# Underwater_ROV_ESCS_asc.net
KiCad netlist of a schematic drawn in Altium Designer
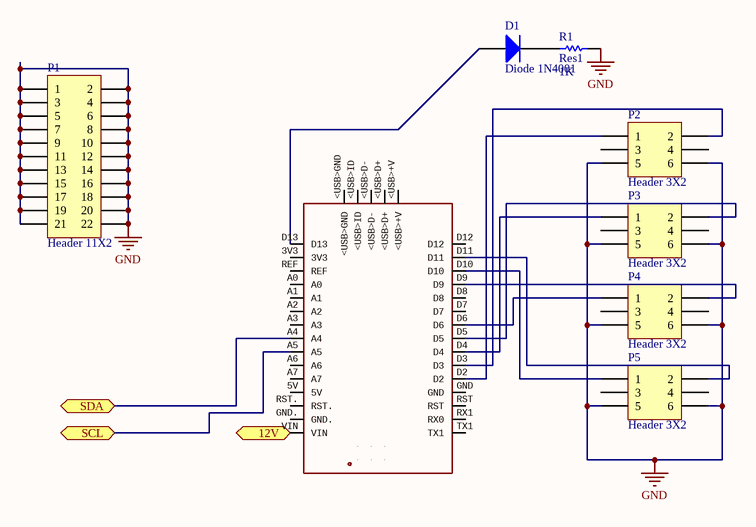
[diagram p0: Underwater_ROV_ESCS_asc.SchDoc]

(export (version "E")
  (design (tool "Eeschema 10.0.6"))
  (components
    (comp (ref "D1")
      (value "Diode 1N4001")
      (footprint "DO-41")
      (description "1 Amp General Purpose Rectifier")
      (fields (field (name "PUBLISHER") "Altium Limited"))
      (libsource (lib "Miscellaneous Devices") (part "Diode 1N4001"))
    )
    (comp (ref "Nano_ESC")
      (value "Device for representing an Arduino Nano board with a footprint in an EAGLE design. Created by Dave Young for Element14. More EAGLE documentation at: http://www.element14.com/community/community/knode/cadsoft_eagle")
      (footprint "ARDUINO_NANO")
      (libsource (lib "E14_Arduino_revC") (part "ARDUINO_NANO"))
    )
    (comp (ref "P1")
      (value "Header 11X2")
      (footprint "HDR2X11")
      (description "Header, 11-Pin, Dual row")
      (fields (field (name "PUBLISHER") "Altium Limited"))
      (libsource (lib "Miscellaneous Connectors") (part "Header 11X2"))
    )
    (comp (ref "P2")
      (value "Header 3X2")
      (footprint "HDR2X3")
      (description "Header, 3-Pin, Dual row")
      (fields (field (name "PUBLISHER") "Altium Limited"))
      (libsource (lib "Miscellaneous Connectors") (part "Header 3X2"))
    )
    (comp (ref "P3")
      (value "Header 3X2")
      (footprint "HDR2X3")
      (description "Header, 3-Pin, Dual row")
      (fields (field (name "PUBLISHER") "Altium Limited"))
      (libsource (lib "Miscellaneous Connectors") (part "Header 3X2"))
    )
    (comp (ref "P4")
      (value "Header 3X2")
      (footprint "HDR2X3")
      (description "Header, 3-Pin, Dual row")
      (fields (field (name "PUBLISHER") "Altium Limited"))
      (libsource (lib "Miscellaneous Connectors") (part "Header 3X2"))
    )
    (comp (ref "P5")
      (value "Header 3X2")
      (footprint "HDR2X3")
      (description "Header, 3-Pin, Dual row")
      (fields (field (name "PUBLISHER") "Altium Limited"))
      (libsource (lib "Miscellaneous Connectors") (part "Header 3X2"))
    )
    (comp (ref "R1")
      (value "Res1")
      (footprint "AXIAL-0.3")
      (description "Resistor")
      (fields (field (name "ALTIUM_VALUE") "1K") (field (name "PUBLISHER") "Altium Limited"))
      (libsource (lib "Miscellaneous Devices") (part "Res1"))
    )
  )
  (nets
    (net (code "1") (name "/12V") (class "Default")
      (node (ref "Nano_ESC") (pin "VIN") (pinfunction "VIN_VIN") (pintype "passive"))
    )
    (net (code "2") (name "/SCL") (class "Default")
      (node (ref "Nano_ESC") (pin "A5") (pinfunction "A5_A5") (pintype "passive"))
    )
    (net (code "3") (name "/SDA") (class "Default")
      (node (ref "Nano_ESC") (pin "A4") (pinfunction "A4_A4") (pintype "passive"))
    )
    (net (code "4") (name "GND") (class "Default")
      (node (ref "P1") (pin "1") (pinfunction "1_1") (pintype "passive"))
      (node (ref "P1") (pin "10") (pinfunction "10_10") (pintype "passive"))
      (node (ref "P1") (pin "11") (pinfunction "11_11") (pintype "passive"))
      (node (ref "P1") (pin "12") (pinfunction "12_12") (pintype "passive"))
      (node (ref "P1") (pin "13") (pinfunction "13_13") (pintype "passive"))
      (node (ref "P1") (pin "14") (pinfunction "14_14") (pintype "passive"))
      (node (ref "P1") (pin "15") (pinfunction "15_15") (pintype "passive"))
      (node (ref "P1") (pin "16") (pinfunction "16_16") (pintype "passive"))
      (node (ref "P1") (pin "17") (pinfunction "17_17") (pintype "passive"))
      (node (ref "P1") (pin "18") (pinfunction "18_18") (pintype "passive"))
      (node (ref "P1") (pin "19") (pinfunction "19_19") (pintype "passive"))
      (node (ref "P1") (pin "2") (pinfunction "2_2") (pintype "passive"))
      (node (ref "P1") (pin "20") (pinfunction "20_20") (pintype "passive"))
      (node (ref "P1") (pin "21") (pinfunction "21_21") (pintype "passive"))
      (node (ref "P1") (pin "22") (pinfunction "22_22") (pintype "passive"))
      (node (ref "P1") (pin "3") (pinfunction "3_3") (pintype "passive"))
      (node (ref "P1") (pin "4") (pinfunction "4_4") (pintype "passive"))
      (node (ref "P1") (pin "5") (pinfunction "5_5") (pintype "passive"))
      (node (ref "P1") (pin "6") (pinfunction "6_6") (pintype "passive"))
      (node (ref "P1") (pin "7") (pinfunction "7_7") (pintype "passive"))
      (node (ref "P1") (pin "8") (pinfunction "8_8") (pintype "passive"))
      (node (ref "P1") (pin "9") (pinfunction "9_9") (pintype "passive"))
      (node (ref "P2") (pin "5") (pinfunction "5_5") (pintype "passive"))
      (node (ref "P2") (pin "6") (pinfunction "6_6") (pintype "passive"))
      (node (ref "P3") (pin "5") (pinfunction "5_5") (pintype "passive"))
      (node (ref "P3") (pin "6") (pinfunction "6_6") (pintype "passive"))
      (node (ref "P4") (pin "5") (pinfunction "5_5") (pintype "passive"))
      (node (ref "P4") (pin "6") (pinfunction "6_6") (pintype "passive"))
      (node (ref "P5") (pin "5") (pinfunction "5_5") (pintype "passive"))
      (node (ref "P5") (pin "6") (pinfunction "6_6") (pintype "passive"))
      (node (ref "R1") (pin "2") (pinfunction "2_2") (pintype "passive"))
    )
    (net (code "5") (name "Net-(D1-A)") (class "Default")
      (node (ref "D1") (pin "1") (pinfunction "A_1") (pintype "passive"))
      (node (ref "Nano_ESC") (pin "D13") (pinfunction "D13_D13") (pintype "passive"))
    )
    (net (code "6") (name "Net-(D1-K)") (class "Default")
      (node (ref "D1") (pin "2") (pinfunction "K_2") (pintype "passive"))
      (node (ref "R1") (pin "1") (pinfunction "1_1") (pintype "passive"))
    )
    (net (code "7") (name "Net-(Nano_ESC-PadD2)") (class "Default")
      (node (ref "Nano_ESC") (pin "D2") (pinfunction "D2_D2") (pintype "passive"))
      (node (ref "P2") (pin "1") (pinfunction "1_1") (pintype "passive"))
    )
    (net (code "8") (name "Net-(Nano_ESC-PadD3)") (class "Default")
      (node (ref "Nano_ESC") (pin "D3") (pinfunction "D3_D3") (pintype "passive"))
      (node (ref "P2") (pin "2") (pinfunction "2_2") (pintype "passive"))
    )
    (net (code "9") (name "Net-(Nano_ESC-PadD4)") (class "Default")
      (node (ref "Nano_ESC") (pin "D4") (pinfunction "D4_D4") (pintype "passive"))
      (node (ref "P3") (pin "1") (pinfunction "1_1") (pintype "passive"))
    )
    (net (code "10") (name "Net-(Nano_ESC-PadD5)") (class "Default")
      (node (ref "Nano_ESC") (pin "D5") (pinfunction "D5_D5") (pintype "passive"))
      (node (ref "P3") (pin "2") (pinfunction "2_2") (pintype "passive"))
    )
    (net (code "11") (name "Net-(Nano_ESC-PadD6)") (class "Default")
      (node (ref "Nano_ESC") (pin "D6") (pinfunction "D6_D6") (pintype "passive"))
      (node (ref "P4") (pin "1") (pinfunction "1_1") (pintype "passive"))
    )
    (net (code "12") (name "Net-(Nano_ESC-PadD9)") (class "Default")
      (node (ref "Nano_ESC") (pin "D9") (pinfunction "D9_D9") (pintype "passive"))
      (node (ref "P4") (pin "2") (pinfunction "2_2") (pintype "passive"))
    )
    (net (code "13") (name "Net-(Nano_ESC-PadD10)") (class "Default")
      (node (ref "Nano_ESC") (pin "D10") (pinfunction "D10_D10") (pintype "passive"))
      (node (ref "P5") (pin "1") (pinfunction "1_1") (pintype "passive"))
    )
    (net (code "14") (name "Net-(Nano_ESC-PadD11)") (class "Default")
      (node (ref "Nano_ESC") (pin "D11") (pinfunction "D11_D11") (pintype "passive"))
      (node (ref "P5") (pin "2") (pinfunction "2_2") (pintype "passive"))
    )
    (net (code "15") (name "unconnected-(Nano_ESC-Pad3V3)") (class "Default")
      (node (ref "Nano_ESC") (pin "3V3") (pinfunction "3V3_3V3") (pintype "passive"))
    )
    (net (code "16") (name "unconnected-(Nano_ESC-Pad5V)") (class "Default")
      (node (ref "Nano_ESC") (pin "5V") (pinfunction "5V_5V") (pintype "passive"))
    )
    (net (code "17") (name "unconnected-(Nano_ESC-Pad5V.)") (class "Default")
      (node (ref "Nano_ESC") (pin "5V.") (pinfunction "5V._5V.") (pintype "passive"))
    )
    (net (code "18") (name "unconnected-(Nano_ESC-Pad<USB>+V)") (class "Default")
      (node (ref "Nano_ESC") (pin "<USB>+V") (pinfunction "<USB>+V_<USB>+V") (pintype "passive"))
    )
    (net (code "19") (name "unconnected-(Nano_ESC-Pad<USB>D+)") (class "Default")
      (node (ref "Nano_ESC") (pin "<USB>D+") (pinfunction "<USB>D+_<USB>D+") (pintype "passive"))
    )
    (net (code "20") (name "unconnected-(Nano_ESC-Pad<USB>D-)") (class "Default")
      (node (ref "Nano_ESC") (pin "<USB>D-") (pinfunction "<USB>D-_<USB>D-") (pintype "passive"))
    )
    (net (code "21") (name "unconnected-(Nano_ESC-Pad<USB>GND)") (class "Default")
      (node (ref "Nano_ESC") (pin "<USB>GND") (pinfunction "<USB>GND_<USB>GND") (pintype "passive"))
    )
    (net (code "22") (name "unconnected-(Nano_ESC-Pad<USB>ID)") (class "Default")
      (node (ref "Nano_ESC") (pin "<USB>ID") (pinfunction "<USB>ID_<USB>ID") (pintype "passive"))
    )
    (net (code "23") (name "unconnected-(Nano_ESC-PadA0)") (class "Default")
      (node (ref "Nano_ESC") (pin "A0") (pinfunction "A0_A0") (pintype "passive"))
    )
    (net (code "24") (name "unconnected-(Nano_ESC-PadA1)") (class "Default")
      (node (ref "Nano_ESC") (pin "A1") (pinfunction "A1_A1") (pintype "passive"))
    )
    (net (code "25") (name "unconnected-(Nano_ESC-PadA2)") (class "Default")
      (node (ref "Nano_ESC") (pin "A2") (pinfunction "A2_A2") (pintype "passive"))
    )
    (net (code "26") (name "unconnected-(Nano_ESC-PadA3)") (class "Default")
      (node (ref "Nano_ESC") (pin "A3") (pinfunction "A3_A3") (pintype "passive"))
    )
    (net (code "27") (name "unconnected-(Nano_ESC-PadA6)") (class "Default")
      (node (ref "Nano_ESC") (pin "A6") (pinfunction "A6_A6") (pintype "passive"))
    )
    (net (code "28") (name "unconnected-(Nano_ESC-PadA7)") (class "Default")
      (node (ref "Nano_ESC") (pin "A7") (pinfunction "A7_A7") (pintype "passive"))
    )
    (net (code "29") (name "unconnected-(Nano_ESC-PadD7)") (class "Default")
      (node (ref "Nano_ESC") (pin "D7") (pinfunction "D7_D7") (pintype "passive"))
    )
    (net (code "30") (name "unconnected-(Nano_ESC-PadD8)") (class "Default")
      (node (ref "Nano_ESC") (pin "D8") (pinfunction "D8_D8") (pintype "passive"))
    )
    (net (code "31") (name "unconnected-(Nano_ESC-PadD12)") (class "Default")
      (node (ref "Nano_ESC") (pin "D12") (pinfunction "D12_D12") (pintype "passive"))
    )
    (net (code "32") (name "unconnected-(Nano_ESC-PadGND)") (class "Default")
      (node (ref "Nano_ESC") (pin "GND") (pinfunction "GND_GND") (pintype "passive"))
    )
    (net (code "33") (name "unconnected-(Nano_ESC-PadGND.)") (class "Default")
      (node (ref "Nano_ESC") (pin "GND.") (pinfunction "GND._GND.") (pintype "passive"))
    )
    (net (code "34") (name "unconnected-(Nano_ESC-PadGND_)") (class "Default")
      (node (ref "Nano_ESC") (pin "GND_") (pinfunction "GND__GND_") (pintype "passive"))
    )
    (net (code "35") (name "unconnected-(Nano_ESC-PadMISO)") (class "Default")
      (node (ref "Nano_ESC") (pin "MISO") (pinfunction "MISO_MISO") (pintype "passive"))
    )
    (net (code "36") (name "unconnected-(Nano_ESC-PadMOSI)") (class "Default")
      (node (ref "Nano_ESC") (pin "MOSI") (pinfunction "MOSI_MOSI") (pintype "passive"))
    )
    (net (code "37") (name "unconnected-(Nano_ESC-PadREF)") (class "Default")
      (node (ref "Nano_ESC") (pin "REF") (pinfunction "REF_REF") (pintype "passive"))
    )
    (net (code "38") (name "unconnected-(Nano_ESC-PadRESET..)") (class "Default")
      (node (ref "Nano_ESC") (pin "RESET..") (pinfunction "RESET.._RESET..") (pintype "passive"))
    )
    (net (code "39") (name "unconnected-(Nano_ESC-PadRST)") (class "Default")
      (node (ref "Nano_ESC") (pin "RST") (pinfunction "RST_RST") (pintype "passive"))
    )
    (net (code "40") (name "unconnected-(Nano_ESC-PadRST.)") (class "Default")
      (node (ref "Nano_ESC") (pin "RST.") (pinfunction "RST._RST.") (pintype "passive"))
    )
    (net (code "41") (name "unconnected-(Nano_ESC-PadSCK)") (class "Default")
      (node (ref "Nano_ESC") (pin "SCK") (pinfunction "SCK_SCK") (pintype "passive"))
    )
    (net (code "42") (name "unconnected-(Nano_ESC-PadTX1)") (class "Default")
      (node (ref "Nano_ESC") (pin "TX1") (pinfunction "TX1_TX1") (pintype "passive"))
    )
    (net (code "43") (name "unconnected-(Nano_ESC-RX0-PadRX1)") (class "Default")
      (node (ref "Nano_ESC") (pin "RX1") (pinfunction "RX0_RX1") (pintype "passive"))
    )
    (net (code "44") (name "unconnected-(P2-Pad3)") (class "Default")
      (node (ref "P2") (pin "3") (pinfunction "3_3") (pintype "passive"))
    )
    (net (code "45") (name "unconnected-(P2-Pad4)") (class "Default")
      (node (ref "P2") (pin "4") (pinfunction "4_4") (pintype "passive"))
    )
    (net (code "46") (name "unconnected-(P3-Pad3)") (class "Default")
      (node (ref "P3") (pin "3") (pinfunction "3_3") (pintype "passive"))
    )
    (net (code "47") (name "unconnected-(P3-Pad4)") (class "Default")
      (node (ref "P3") (pin "4") (pinfunction "4_4") (pintype "passive"))
    )
    (net (code "48") (name "unconnected-(P4-Pad3)") (class "Default")
      (node (ref "P4") (pin "3") (pinfunction "3_3") (pintype "passive"))
    )
    (net (code "49") (name "unconnected-(P4-Pad4)") (class "Default")
      (node (ref "P4") (pin "4") (pinfunction "4_4") (pintype "passive"))
    )
    (net (code "50") (name "unconnected-(P5-Pad3)") (class "Default")
      (node (ref "P5") (pin "3") (pinfunction "3_3") (pintype "passive"))
    )
    (net (code "51") (name "unconnected-(P5-Pad4)") (class "Default")
      (node (ref "P5") (pin "4") (pinfunction "4_4") (pintype "passive"))
    )
  )
)
